# de0-orpsoc.net
KiCad netlist of a schematic drawn in EAGLE
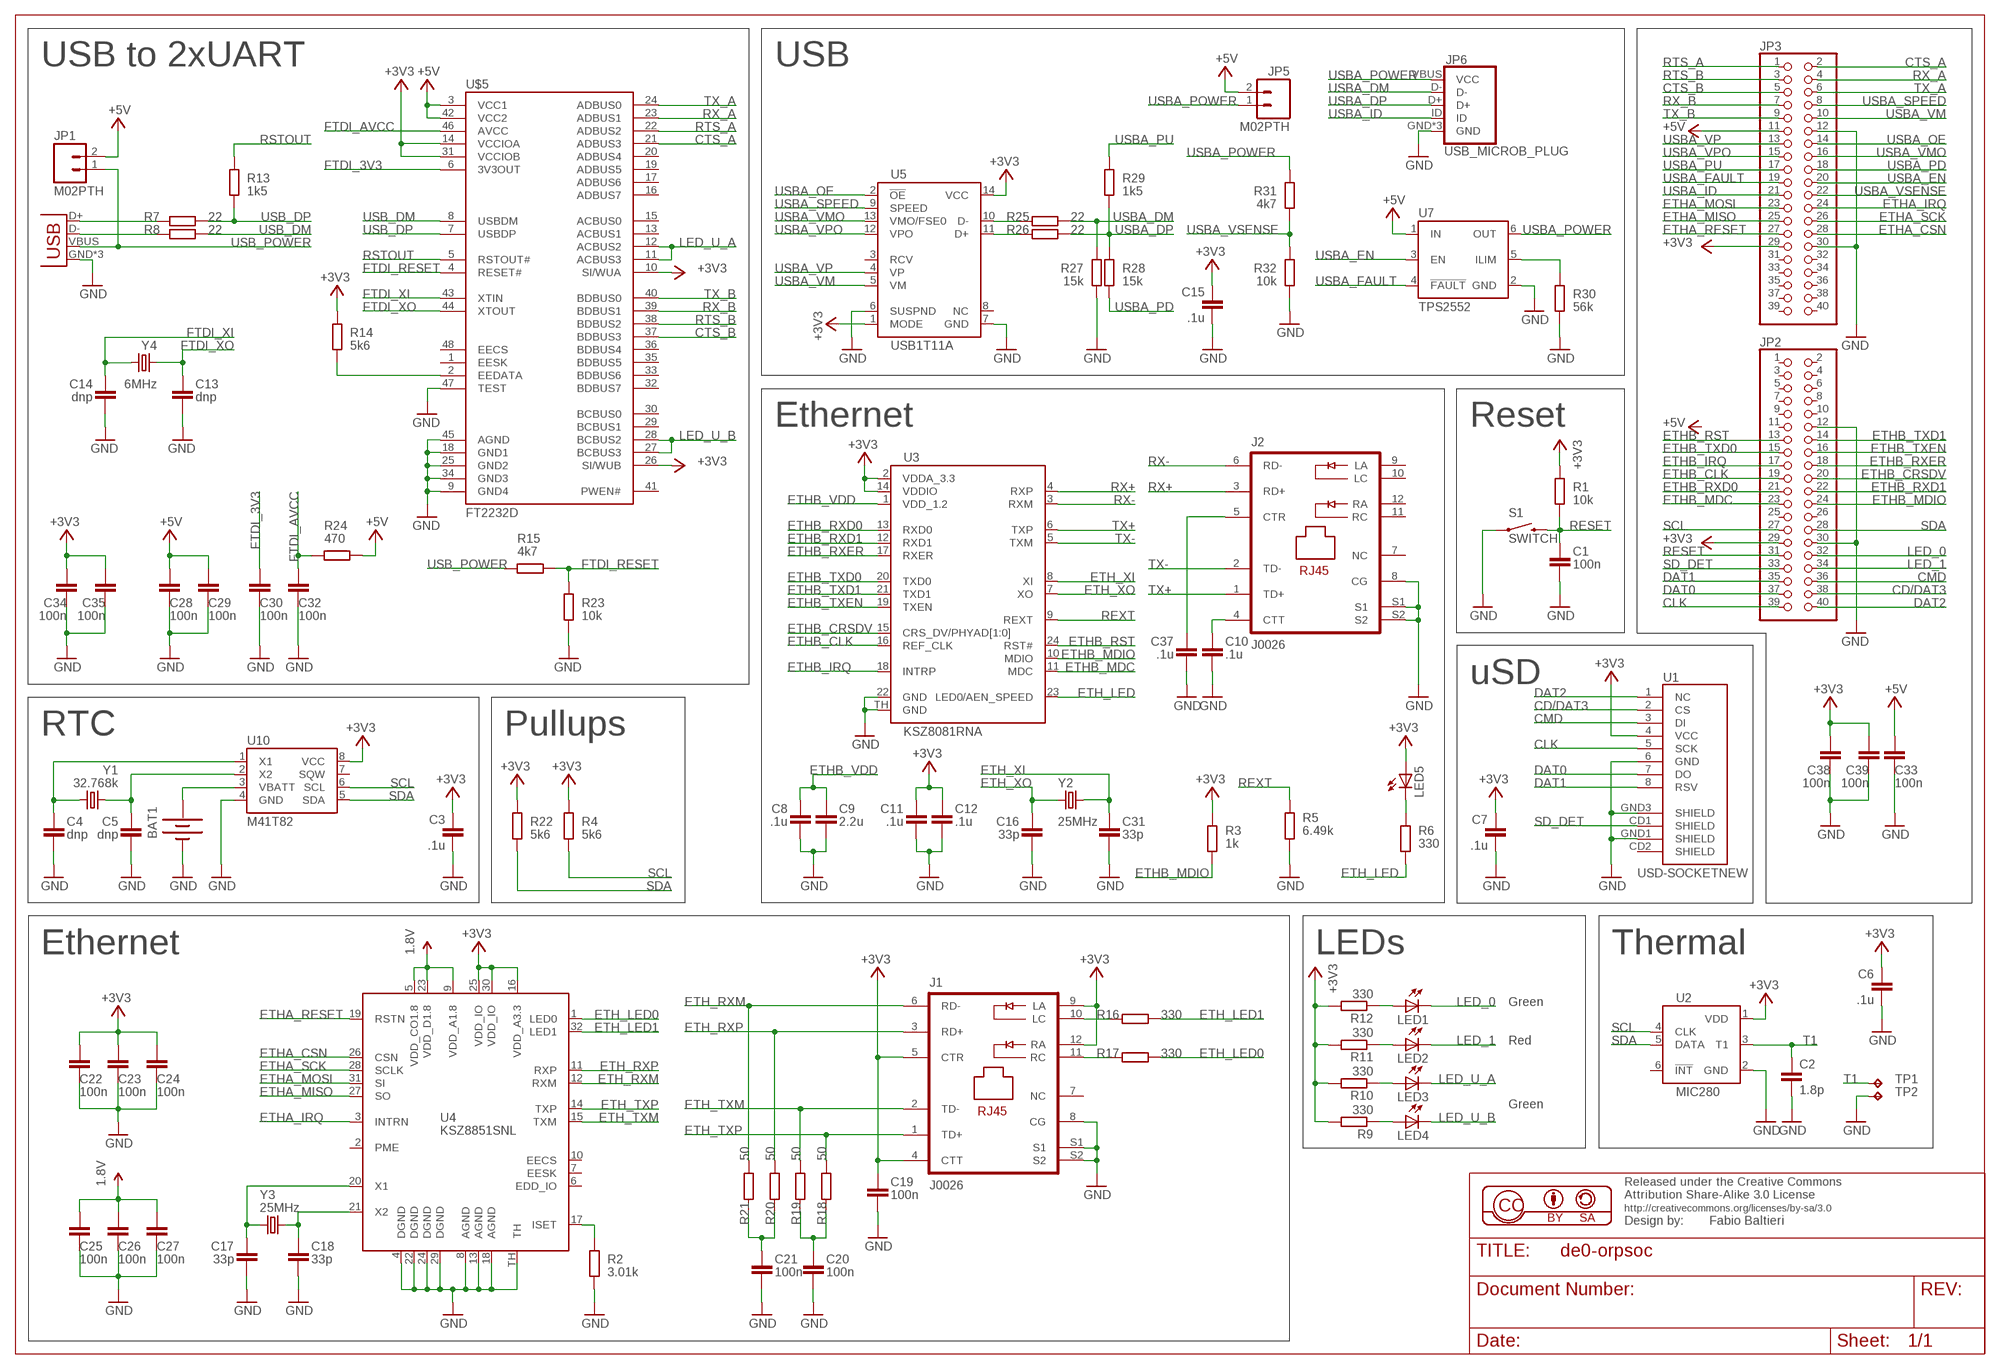
[diagram p0: schematic, sheet 1]

(export (version "E")
  (design (tool "Eeschema 10.0.6"))
  (components
    (comp (ref "BAT1")
      (value "BATTERY12PTH")
      (footprint "eagle-import:BATTCON_12MM_PTH")
      (libsource (lib "eagle-import") (part "BATTERY12PTH"))
    )
    (comp (ref "C1")
      (value "100n")
      (footprint "eagle-import:C0603")
      (libsource (lib "eagle-import") (part "C-EUC0603"))
    )
    (comp (ref "C2")
      (value "1.8p")
      (footprint "eagle-import:C0603")
      (libsource (lib "eagle-import") (part "C-EUC0603"))
    )
    (comp (ref "C3")
      (value ".1u")
      (footprint "eagle-import:C0603")
      (libsource (lib "eagle-import") (part "C-EUC0603"))
    )
    (comp (ref "C4")
      (value "dnp")
      (footprint "eagle-import:C0603")
      (libsource (lib "eagle-import") (part "C-EUC0603"))
    )
    (comp (ref "C5")
      (value "dnp")
      (footprint "eagle-import:C0603")
      (libsource (lib "eagle-import") (part "C-EUC0603"))
    )
    (comp (ref "C6")
      (value ".1u")
      (footprint "eagle-import:C0603")
      (libsource (lib "eagle-import") (part "C-EUC0603"))
    )
    (comp (ref "C7")
      (value ".1u")
      (footprint "eagle-import:C0603")
      (libsource (lib "eagle-import") (part "C-EUC0603"))
    )
    (comp (ref "C8")
      (value ".1u")
      (footprint "eagle-import:C0603")
      (libsource (lib "eagle-import") (part "C-EUC0603"))
    )
    (comp (ref "C9")
      (value "2.2u")
      (footprint "eagle-import:C0603")
      (libsource (lib "eagle-import") (part "C-EUC0603"))
    )
    (comp (ref "C10")
      (value ".1u")
      (footprint "eagle-import:C0603")
      (libsource (lib "eagle-import") (part "C-EUC0603"))
    )
    (comp (ref "C11")
      (value ".1u")
      (footprint "eagle-import:C0603")
      (libsource (lib "eagle-import") (part "C-EUC0603"))
    )
    (comp (ref "C12")
      (value ".1u")
      (footprint "eagle-import:C0603")
      (libsource (lib "eagle-import") (part "C-EUC0603"))
    )
    (comp (ref "C13")
      (value "dnp")
      (footprint "eagle-import:C0603")
      (libsource (lib "eagle-import") (part "C-EUC0603"))
    )
    (comp (ref "C14")
      (value "dnp")
      (footprint "eagle-import:C0603")
      (libsource (lib "eagle-import") (part "C-EUC0603"))
    )
    (comp (ref "C15")
      (value ".1u")
      (footprint "eagle-import:C0603")
      (libsource (lib "eagle-import") (part "C-EUC0603"))
    )
    (comp (ref "C16")
      (value "33p")
      (footprint "eagle-import:C0603")
      (libsource (lib "eagle-import") (part "C-EUC0603"))
    )
    (comp (ref "C17")
      (value "33p")
      (footprint "eagle-import:C0603")
      (libsource (lib "eagle-import") (part "C-EUC0603"))
    )
    (comp (ref "C18")
      (value "33p")
      (footprint "eagle-import:C0603")
      (libsource (lib "eagle-import") (part "C-EUC0603"))
    )
    (comp (ref "C19")
      (value "100n")
      (footprint "eagle-import:C0603")
      (libsource (lib "eagle-import") (part "C-EUC0603"))
    )
    (comp (ref "C20")
      (value "100n")
      (footprint "eagle-import:C0603")
      (libsource (lib "eagle-import") (part "C-EUC0603"))
    )
    (comp (ref "C21")
      (value "100n")
      (footprint "eagle-import:C0603")
      (libsource (lib "eagle-import") (part "C-EUC0603"))
    )
    (comp (ref "C22")
      (value "100n")
      (footprint "eagle-import:C0603")
      (libsource (lib "eagle-import") (part "C-EUC0603"))
    )
    (comp (ref "C23")
      (value "100n")
      (footprint "eagle-import:C0603")
      (libsource (lib "eagle-import") (part "C-EUC0603"))
    )
    (comp (ref "C24")
      (value "100n")
      (footprint "eagle-import:C0603")
      (libsource (lib "eagle-import") (part "C-EUC0603"))
    )
    (comp (ref "C25")
      (value "100n")
      (footprint "eagle-import:C0603")
      (libsource (lib "eagle-import") (part "C-EUC0603"))
    )
    (comp (ref "C26")
      (value "100n")
      (footprint "eagle-import:C0603")
      (libsource (lib "eagle-import") (part "C-EUC0603"))
    )
    (comp (ref "C27")
      (value "100n")
      (footprint "eagle-import:C0603")
      (libsource (lib "eagle-import") (part "C-EUC0603"))
    )
    (comp (ref "C28")
      (value "100n")
      (footprint "eagle-import:C0603")
      (libsource (lib "eagle-import") (part "C-EUC0603"))
    )
    (comp (ref "C29")
      (value "100n")
      (footprint "eagle-import:C0603")
      (libsource (lib "eagle-import") (part "C-EUC0603"))
    )
    (comp (ref "C30")
      (value "100n")
      (footprint "eagle-import:C0603")
      (libsource (lib "eagle-import") (part "C-EUC0603"))
    )
    (comp (ref "C31")
      (value "33p")
      (footprint "eagle-import:C0603")
      (libsource (lib "eagle-import") (part "C-EUC0603"))
    )
    (comp (ref "C32")
      (value "100n")
      (footprint "eagle-import:C0603")
      (libsource (lib "eagle-import") (part "C-EUC0603"))
    )
    (comp (ref "C33")
      (value "100n")
      (footprint "eagle-import:C0603")
      (libsource (lib "eagle-import") (part "C-EUC0603"))
    )
    (comp (ref "C34")
      (value "100n")
      (footprint "eagle-import:C0603")
      (libsource (lib "eagle-import") (part "C-EUC0603"))
    )
    (comp (ref "C35")
      (value "100n")
      (footprint "eagle-import:C0603")
      (libsource (lib "eagle-import") (part "C-EUC0603"))
    )
    (comp (ref "C37")
      (value ".1u")
      (footprint "eagle-import:C0603")
      (libsource (lib "eagle-import") (part "C-EUC0603"))
    )
    (comp (ref "C38")
      (value "100n")
      (footprint "eagle-import:C0603")
      (libsource (lib "eagle-import") (part "C-EUC0603"))
    )
    (comp (ref "C39")
      (value "100n")
      (footprint "eagle-import:C0603")
      (libsource (lib "eagle-import") (part "C-EUC0603"))
    )
    (comp (ref "J1")
      (value "J0026")
      (footprint "eagle-import:PJ-J0")
      (libsource (lib "eagle-import") (part "J0026"))
    )
    (comp (ref "J2")
      (value "J0026")
      (footprint "eagle-import:PJ-J0")
      (libsource (lib "eagle-import") (part "J0026"))
    )
    (comp (ref "JP1")
      (value "M02PTH")
      (footprint "eagle-import:1X02")
      (libsource (lib "eagle-import") (part "M02PTH"))
    )
    (comp (ref "JP2")
      (value "PINHD-2X20")
      (footprint "eagle-import:2X20")
      (libsource (lib "eagle-import") (part "PINHD-2X20"))
    )
    (comp (ref "JP3")
      (value "PINHD-2X20")
      (footprint "eagle-import:2X20")
      (libsource (lib "eagle-import") (part "PINHD-2X20"))
    )
    (comp (ref "JP5")
      (value "M02PTH")
      (footprint "eagle-import:1X02")
      (libsource (lib "eagle-import") (part "M02PTH"))
    )
    (comp (ref "JP6")
      (value "USB_MICROB_PLUG")
      (footprint "eagle-import:USB-MICROB")
      (libsource (lib "eagle-import") (part "USB_MICROB_PLUG"))
    )
    (comp (ref "JP10")
      (value "USB-MICROB")
      (footprint "eagle-import:USB-MICROB")
      (libsource (lib "eagle-import") (part "USB-MICROB"))
    )
    (comp (ref "LED1")
      (value "LEDCHIPLED_0805")
      (footprint "eagle-import:CHIPLED_0805")
      (libsource (lib "eagle-import") (part "LEDCHIPLED_0805"))
    )
    (comp (ref "LED2")
      (value "LEDCHIPLED_0805")
      (footprint "eagle-import:CHIPLED_0805")
      (libsource (lib "eagle-import") (part "LEDCHIPLED_0805"))
    )
    (comp (ref "LED3")
      (value "LEDCHIPLED_0805")
      (footprint "eagle-import:CHIPLED_0805")
      (libsource (lib "eagle-import") (part "LEDCHIPLED_0805"))
    )
    (comp (ref "LED4")
      (value "LEDCHIPLED_0805")
      (footprint "eagle-import:CHIPLED_0805")
      (libsource (lib "eagle-import") (part "LEDCHIPLED_0805"))
    )
    (comp (ref "LED5")
      (value "LEDCHIPLED_0805")
      (footprint "eagle-import:CHIPLED_0805")
      (libsource (lib "eagle-import") (part "LEDCHIPLED_0805"))
    )
    (comp (ref "R1")
      (value "10k")
      (footprint "eagle-import:R0603")
      (libsource (lib "eagle-import") (part "R-EU_R0603"))
    )
    (comp (ref "R2")
      (value "3.01k")
      (footprint "eagle-import:R0603")
      (libsource (lib "eagle-import") (part "R-EU_R0603"))
    )
    (comp (ref "R3")
      (value "1k")
      (footprint "eagle-import:R0603")
      (libsource (lib "eagle-import") (part "R-EU_R0603"))
    )
    (comp (ref "R4")
      (value "5k6")
      (footprint "eagle-import:R0603")
      (libsource (lib "eagle-import") (part "R-EU_R0603"))
    )
    (comp (ref "R5")
      (value "6.49k")
      (footprint "eagle-import:R0603")
      (libsource (lib "eagle-import") (part "R-EU_R0603"))
    )
    (comp (ref "R6")
      (value "330")
      (footprint "eagle-import:R0603")
      (libsource (lib "eagle-import") (part "R-EU_R0603"))
    )
    (comp (ref "R7")
      (value "22")
      (footprint "eagle-import:R0603")
      (libsource (lib "eagle-import") (part "R-EU_R0603"))
    )
    (comp (ref "R8")
      (value "22")
      (footprint "eagle-import:R0603")
      (libsource (lib "eagle-import") (part "R-EU_R0603"))
    )
    (comp (ref "R9")
      (value "330")
      (footprint "eagle-import:R0603")
      (libsource (lib "eagle-import") (part "R-EU_R0603"))
    )
    (comp (ref "R10")
      (value "330")
      (footprint "eagle-import:R0603")
      (libsource (lib "eagle-import") (part "R-EU_R0603"))
    )
    (comp (ref "R11")
      (value "330")
      (footprint "eagle-import:R0603")
      (libsource (lib "eagle-import") (part "R-EU_R0603"))
    )
    (comp (ref "R12")
      (value "330")
      (footprint "eagle-import:R0603")
      (libsource (lib "eagle-import") (part "R-EU_R0603"))
    )
    (comp (ref "R13")
      (value "1k5")
      (footprint "eagle-import:R0603")
      (libsource (lib "eagle-import") (part "R-EU_R0603"))
    )
    (comp (ref "R14")
      (value "5k6")
      (footprint "eagle-import:R0603")
      (libsource (lib "eagle-import") (part "R-EU_R0603"))
    )
    (comp (ref "R15")
      (value "4k7")
      (footprint "eagle-import:R0603")
      (libsource (lib "eagle-import") (part "R-EU_R0603"))
    )
    (comp (ref "R16")
      (value "330")
      (footprint "eagle-import:R0603")
      (libsource (lib "eagle-import") (part "R-EU_R0603"))
    )
    (comp (ref "R17")
      (value "330")
      (footprint "eagle-import:R0603")
      (libsource (lib "eagle-import") (part "R-EU_R0603"))
    )
    (comp (ref "R18")
      (value "50")
      (footprint "eagle-import:R0603")
      (libsource (lib "eagle-import") (part "R-EU_R0603"))
    )
    (comp (ref "R19")
      (value "50")
      (footprint "eagle-import:R0603")
      (libsource (lib "eagle-import") (part "R-EU_R0603"))
    )
    (comp (ref "R20")
      (value "50")
      (footprint "eagle-import:R0603")
      (libsource (lib "eagle-import") (part "R-EU_R0603"))
    )
    (comp (ref "R21")
      (value "50")
      (footprint "eagle-import:R0603")
      (libsource (lib "eagle-import") (part "R-EU_R0603"))
    )
    (comp (ref "R22")
      (value "5k6")
      (footprint "eagle-import:R0603")
      (libsource (lib "eagle-import") (part "R-EU_R0603"))
    )
    (comp (ref "R23")
      (value "10k")
      (footprint "eagle-import:R0603")
      (libsource (lib "eagle-import") (part "R-EU_R0603"))
    )
    (comp (ref "R24")
      (value "470")
      (footprint "eagle-import:R0603")
      (libsource (lib "eagle-import") (part "R-EU_R0603"))
    )
    (comp (ref "R25")
      (value "22")
      (footprint "eagle-import:R0603")
      (libsource (lib "eagle-import") (part "R-EU_R0603"))
    )
    (comp (ref "R26")
      (value "22")
      (footprint "eagle-import:R0603")
      (libsource (lib "eagle-import") (part "R-EU_R0603"))
    )
    (comp (ref "R27")
      (value "15k")
      (footprint "eagle-import:R0603")
      (libsource (lib "eagle-import") (part "R-EU_R0603"))
    )
    (comp (ref "R28")
      (value "15k")
      (footprint "eagle-import:R0603")
      (libsource (lib "eagle-import") (part "R-EU_R0603"))
    )
    (comp (ref "R29")
      (value "1k5")
      (footprint "eagle-import:R0603")
      (libsource (lib "eagle-import") (part "R-EU_R0603"))
    )
    (comp (ref "R30")
      (value "56k")
      (footprint "eagle-import:R0603")
      (libsource (lib "eagle-import") (part "R-EU_R0603"))
    )
    (comp (ref "R31")
      (value "4k7")
      (footprint "eagle-import:R0603")
      (libsource (lib "eagle-import") (part "R-EU_R0603"))
    )
    (comp (ref "R32")
      (value "10k")
      (footprint "eagle-import:R0603")
      (libsource (lib "eagle-import") (part "R-EU_R0603"))
    )
    (comp (ref "S1")
      (value "SWITCH")
      (footprint "eagle-import:TACTILE_SWITCH_SMD")
      (libsource (lib "eagle-import") (part "SWITCH-MOMENTARY-2SMD"))
    )
    (comp (ref "TP1")
      (value "TPTP12R")
      (footprint "eagle-import:TP12R")
      (libsource (lib "eagle-import") (part "TPTP12R"))
    )
    (comp (ref "TP2")
      (value "TPTP12R")
      (footprint "eagle-import:TP12R")
      (libsource (lib "eagle-import") (part "TPTP12R"))
    )
    (comp (ref "U$5")
      (value "FT2232D")
      (footprint "eagle-import:LQFP-48")
      (libsource (lib "eagle-import") (part "FT2232D"))
    )
    (comp (ref "U1")
      (value "USD-SOCKETNEW")
      (footprint "eagle-import:MICRO-SD-SOCKET-PP")
      (libsource (lib "eagle-import") (part "USD-SOCKETNEW"))
    )
    (comp (ref "U2")
      (value "MIC280")
      (footprint "eagle-import:SOT23-6L")
      (libsource (lib "eagle-import") (part "MIC280"))
    )
    (comp (ref "U3")
      (value "KSZ8081RNA")
      (footprint "eagle-import:QFN24")
      (libsource (lib "eagle-import") (part "KSZ8081"))
    )
    (comp (ref "U4")
      (value "KSZ8851SNL")
      (footprint "eagle-import:MLF32-TH")
      (libsource (lib "eagle-import") (part "KSZ8851SNL"))
    )
    (comp (ref "U5")
      (value "USB1T11A")
      (footprint "eagle-import:SOIC14")
      (libsource (lib "eagle-import") (part "USB1T11A"))
    )
    (comp (ref "U7")
      (value "TPS2552")
      (footprint "eagle-import:SOT23-6L")
      (libsource (lib "eagle-import") (part "TPS2552"))
    )
    (comp (ref "U10")
      (value "M41T82")
      (footprint "eagle-import:SO08")
      (libsource (lib "eagle-import") (part "DS1307SO8"))
    )
    (comp (ref "Y1")
      (value "32.768k")
      (footprint "eagle-import:CRYSTAL-32KHZ-SMD")
      (libsource (lib "eagle-import") (part "SparkFun-FreqCtrl_CRYSTAL32-SMD"))
    )
    (comp (ref "Y2")
      (value "25MHz")
      (footprint "eagle-import:CRYSTAL-SMD-5X3")
      (libsource (lib "eagle-import") (part "CRYSTAL5X3"))
    )
    (comp (ref "Y3")
      (value "25MHz")
      (footprint "eagle-import:CRYSTAL-SMD-5X3")
      (libsource (lib "eagle-import") (part "CRYSTAL5X3"))
    )
    (comp (ref "Y4")
      (value "6MHz")
      (footprint "eagle-import:CRYSTAL-SMD-5X3")
      (libsource (lib "eagle-import") (part "CRYSTAL5X3"))
    )
  )
  (nets
    (net (code "1") (name "+3V3") (class "Default")
      (node (ref "C11") (pin "1") (pinfunction "1_1") (pintype "passive"))
      (node (ref "C12") (pin "1") (pinfunction "1_1") (pintype "passive"))
      (node (ref "C15") (pin "1") (pinfunction "1_1") (pintype "passive"))
      (node (ref "C19") (pin "1") (pinfunction "1_1") (pintype "passive"))
      (node (ref "C22") (pin "1") (pinfunction "1_1") (pintype "passive"))
      (node (ref "C23") (pin "1") (pinfunction "1_1") (pintype "passive"))
      (node (ref "C24") (pin "1") (pinfunction "1_1") (pintype "passive"))
      (node (ref "C3") (pin "1") (pinfunction "1_1") (pintype "passive"))
      (node (ref "C34") (pin "1") (pinfunction "1_1") (pintype "passive"))
      (node (ref "C35") (pin "1") (pinfunction "1_1") (pintype "passive"))
      (node (ref "C38") (pin "1") (pinfunction "1_1") (pintype "passive"))
      (node (ref "C39") (pin "1") (pinfunction "1_1") (pintype "passive"))
      (node (ref "C6") (pin "1") (pinfunction "1_1") (pintype "passive"))
      (node (ref "C7") (pin "1") (pinfunction "1_1") (pintype "passive"))
      (node (ref "J1") (pin "12") (pinfunction "RA_12") (pintype "passive"))
      (node (ref "J1") (pin "4") (pinfunction "CTT_4") (pintype "bidirectional"))
      (node (ref "J1") (pin "5") (pinfunction "CTR_5") (pintype "bidirectional"))
      (node (ref "J1") (pin "9") (pinfunction "LA_9") (pintype "passive"))
      (node (ref "JP2") (pin "29") (pinfunction "29_29") (pintype "passive"))
      (node (ref "JP3") (pin "29") (pinfunction "29_29") (pintype "passive"))
      (node (ref "LED5") (pin "A") (pinfunction "A_A") (pintype "passive"))
      (node (ref "R1") (pin "2") (pinfunction "2_2") (pintype "passive"))
      (node (ref "R10") (pin "2") (pinfunction "2_2") (pintype "passive"))
      (node (ref "R11") (pin "2") (pinfunction "2_2") (pintype "passive"))
      (node (ref "R12") (pin "2") (pinfunction "2_2") (pintype "passive"))
      (node (ref "R14") (pin "1") (pinfunction "1_1") (pintype "passive"))
      (node (ref "R22") (pin "1") (pinfunction "1_1") (pintype "passive"))
      (node (ref "R3") (pin "2") (pinfunction "2_2") (pintype "passive"))
      (node (ref "R4") (pin "1") (pinfunction "1_1") (pintype "passive"))
      (node (ref "R9") (pin "2") (pinfunction "2_2") (pintype "passive"))
      (node (ref "U$5") (pin "10") (pinfunction "SI/WUA_10") (pintype "bidirectional"))
      (node (ref "U$5") (pin "14") (pinfunction "VCCIOA_14") (pintype "power_in"))
      (node (ref "U$5") (pin "26") (pinfunction "SI/WUB_26") (pintype "bidirectional"))
      (node (ref "U$5") (pin "31") (pinfunction "VCCIOB_31") (pintype "bidirectional"))
      (node (ref "U1") (pin "4") (pinfunction "VCC_4") (pintype "bidirectional"))
      (node (ref "U10") (pin "8") (pinfunction "VCC_8") (pintype "bidirectional"))
      (node (ref "U2") (pin "1") (pinfunction "VDD_1") (pintype "bidirectional"))
      (node (ref "U3") (pin "14") (pinfunction "VDDIO_14") (pintype "bidirectional"))
      (node (ref "U3") (pin "2") (pinfunction "VDDA_3.3_2") (pintype "bidirectional"))
      (node (ref "U4") (pin "16") (pinfunction "VDD_A3.3_16") (pintype "bidirectional"))
      (node (ref "U4") (pin "25") (pinfunction "VDD_IO_25") (pintype "bidirectional"))
      (node (ref "U4") (pin "30") (pinfunction "VDD_IO_30") (pintype "bidirectional"))
      (node (ref "U5") (pin "1") (pinfunction "MODE_1") (pintype "bidirectional"))
      (node (ref "U5") (pin "14") (pinfunction "VCC_14") (pintype "bidirectional"))
    )
    (net (code "2") (name "+5V") (class "Default")
      (node (ref "C28") (pin "1") (pinfunction "1_1") (pintype "passive"))
      (node (ref "C29") (pin "1") (pinfunction "1_1") (pintype "passive"))
      (node (ref "C33") (pin "1") (pinfunction "1_1") (pintype "passive"))
      (node (ref "JP1") (pin "2") (pinfunction "2_2") (pintype "passive"))
      (node (ref "JP3") (pin "11") (pinfunction "11_11") (pintype "passive"))
      (node (ref "JP5") (pin "2") (pinfunction "2_2") (pintype "passive"))
      (node (ref "R24") (pin "2") (pinfunction "2_2") (pintype "passive"))
      (node (ref "U$5") (pin "3") (pinfunction "VCC1_3") (pintype "power_in"))
      (node (ref "U$5") (pin "42") (pinfunction "VCC2_42") (pintype "power_in"))
      (node (ref "U7") (pin "1") (pinfunction "IN_1") (pintype "bidirectional"))
    )
    (net (code "3") (name "/CD{slash}DAT3") (class "Default")
      (node (ref "JP2") (pin "38") (pinfunction "38_38") (pintype "passive"))
      (node (ref "U1") (pin "2") (pinfunction "CS_2") (pintype "bidirectional"))
    )
    (net (code "4") (name "/CLK") (class "Default")
      (node (ref "JP2") (pin "39") (pinfunction "39_39") (pintype "passive"))
      (node (ref "U1") (pin "5") (pinfunction "SCK_5") (pintype "bidirectional"))
    )
    (net (code "5") (name "/CMD") (class "Default")
      (node (ref "JP2") (pin "36") (pinfunction "36_36") (pintype "passive"))
      (node (ref "U1") (pin "3") (pinfunction "DI_3") (pintype "bidirectional"))
    )
    (net (code "6") (name "/CTS_A") (class "Default")
      (node (ref "JP3") (pin "2") (pinfunction "2_2") (pintype "passive"))
      (node (ref "U$5") (pin "21") (pinfunction "ADBUS3_21") (pintype "bidirectional"))
    )
    (net (code "7") (name "/CTS_B") (class "Default")
      (node (ref "JP3") (pin "5") (pinfunction "5_5") (pintype "passive"))
      (node (ref "U$5") (pin "37") (pinfunction "BDBUS3_37") (pintype "input"))
    )
    (net (code "8") (name "/DAT0") (class "Default")
      (node (ref "JP2") (pin "37") (pinfunction "37_37") (pintype "passive"))
      (node (ref "U1") (pin "7") (pinfunction "DO_7") (pintype "bidirectional"))
    )
    (net (code "9") (name "/DAT1") (class "Default")
      (node (ref "JP2") (pin "35") (pinfunction "35_35") (pintype "passive"))
      (node (ref "U1") (pin "8") (pinfunction "RSV_8") (pintype "bidirectional"))
    )
    (net (code "10") (name "/DAT2") (class "Default")
      (node (ref "JP2") (pin "40") (pinfunction "40_40") (pintype "passive"))
      (node (ref "U1") (pin "1") (pinfunction "NC_1") (pintype "bidirectional"))
    )
    (net (code "11") (name "/ETHA_CSN") (class "Default")
      (node (ref "JP3") (pin "28") (pinfunction "28_28") (pintype "passive"))
      (node (ref "U4") (pin "26") (pinfunction "CSN_26") (pintype "bidirectional"))
    )
    (net (code "12") (name "/ETHA_IRQ") (class "Default")
      (node (ref "JP3") (pin "24") (pinfunction "24_24") (pintype "passive"))
      (node (ref "U4") (pin "3") (pinfunction "INTRN_3") (pintype "bidirectional"))
    )
    (net (code "13") (name "/ETHA_MISO") (class "Default")
      (node (ref "JP3") (pin "25") (pinfunction "25_25") (pintype "passive"))
      (node (ref "U4") (pin "27") (pinfunction "SO_27") (pintype "bidirectional"))
    )
    (net (code "14") (name "/ETHA_MOSI") (class "Default")
      (node (ref "JP3") (pin "23") (pinfunction "23_23") (pintype "passive"))
      (node (ref "U4") (pin "31") (pinfunction "SI_31") (pintype "bidirectional"))
    )
    (net (code "15") (name "/ETHA_RESET") (class "Default")
      (node (ref "JP3") (pin "27") (pinfunction "27_27") (pintype "passive"))
      (node (ref "U4") (pin "19") (pinfunction "RSTN_19") (pintype "bidirectional"))
    )
    (net (code "16") (name "/ETHA_SCK") (class "Default")
      (node (ref "JP3") (pin "26") (pinfunction "26_26") (pintype "passive"))
      (node (ref "U4") (pin "28") (pinfunction "SCLK_28") (pintype "bidirectional"))
    )
    (net (code "17") (name "/ETHB_CLK") (class "Default")
      (node (ref "JP2") (pin "19") (pinfunction "19_19") (pintype "passive"))
      (node (ref "U3") (pin "16") (pinfunction "REF_CLK_16") (pintype "bidirectional"))
    )
    (net (code "18") (name "/ETHB_CRSDV") (class "Default")
      (node (ref "JP2") (pin "20") (pinfunction "20_20") (pintype "passive"))
      (node (ref "U3") (pin "15") (pinfunction "CRS_DV/PHYAD[1:0]_15") (pintype "bidirectional"))
    )
    (net (code "19") (name "/ETHB_IRQ") (class "Default")
      (node (ref "JP2") (pin "17") (pinfunction "17_17") (pintype "passive"))
      (node (ref "U3") (pin "18") (pinfunction "INTRP_18") (pintype "bidirectional"))
    )
    (net (code "20") (name "/ETHB_MDC") (class "Default")
      (node (ref "JP2") (pin "23") (pinfunction "23_23") (pintype "passive"))
      (node (ref "U3") (pin "11") (pinfunction "MDC_11") (pintype "bidirectional"))
    )
    (net (code "21") (name "/ETHB_MDIO") (class "Default")
      (node (ref "JP2") (pin "24") (pinfunction "24_24") (pintype "passive"))
      (node (ref "R3") (pin "1") (pinfunction "1_1") (pintype "passive"))
      (node (ref "U3") (pin "10") (pinfunction "MDIO_10") (pintype "bidirectional"))
    )
    (net (code "22") (name "/ETHB_RST") (class "Default")
      (node (ref "JP2") (pin "13") (pinfunction "13_13") (pintype "passive"))
      (node (ref "U3") (pin "24") (pinfunction "RST#_24") (pintype "bidirectional"))
    )
    (net (code "23") (name "/ETHB_RXD0") (class "Default")
      (node (ref "JP2") (pin "21") (pinfunction "21_21") (pintype "passive"))
      (node (ref "U3") (pin "13") (pinfunction "RXD0_13") (pintype "bidirectional"))
    )
    (net (code "24") (name "/ETHB_RXD1") (class "Default")
      (node (ref "JP2") (pin "22") (pinfunction "22_22") (pintype "passive"))
      (node (ref "U3") (pin "12") (pinfunction "RXD1_12") (pintype "bidirectional"))
    )
    (net (code "25") (name "/ETHB_RXER") (class "Default")
      (node (ref "JP2") (pin "18") (pinfunction "18_18") (pintype "passive"))
      (node (ref "U3") (pin "17") (pinfunction "RXER_17") (pintype "bidirectional"))
    )
    (net (code "26") (name "/ETHB_TXD0") (class "Default")
      (node (ref "JP2") (pin "15") (pinfunction "15_15") (pintype "passive"))
      (node (ref "U3") (pin "20") (pinfunction "TXD0_20") (pintype "bidirectional"))
    )
    (net (code "27") (name "/ETHB_TXD1") (class "Default")
      (node (ref "JP2") (pin "14") (pinfunction "14_14") (pintype "passive"))
      (node (ref "U3") (pin "21") (pinfunction "TXD1_21") (pintype "bidirectional"))
    )
    (net (code "28") (name "/ETHB_TXEN") (class "Default")
      (node (ref "JP2") (pin "16") (pinfunction "16_16") (pintype "passive"))
      (node (ref "U3") (pin "19") (pinfunction "TXEN_19") (pintype "bidirectional"))
    )
    (net (code "29") (name "/ETHB_VDD") (class "Default")
      (node (ref "C8") (pin "1") (pinfunction "1_1") (pintype "passive"))
      (node (ref "C9") (pin "1") (pinfunction "1_1") (pintype "passive"))
      (node (ref "U3") (pin "1") (pinfunction "VDD_1.2_1") (pintype "bidirectional"))
    )
    (net (code "30") (name "/ETH_LED") (class "Default")
      (node (ref "R6") (pin "1") (pinfunction "1_1") (pintype "passive"))
      (node (ref "U3") (pin "23") (pinfunction "LED0/AEN_SPEED_23") (pintype "bidirectional"))
    )
    (net (code "31") (name "/ETH_LED0") (class "Default")
      (node (ref "R17") (pin "2") (pinfunction "2_2") (pintype "passive"))
      (node (ref "U4") (pin "1") (pinfunction "LED0_1") (pintype "bidirectional"))
    )
    (net (code "32") (name "/ETH_LED1") (class "Default")
      (node (ref "R16") (pin "2") (pinfunction "2_2") (pintype "passive"))
      (node (ref "U4") (pin "32") (pinfunction "LED1_32") (pintype "bidirectional"))
    )
    (net (code "33") (name "/ETH_RXM") (class "Default")
      (node (ref "J1") (pin "6") (pinfunction "RD-_6") (pintype "bidirectional"))
      (node (ref "R21") (pin "2") (pinfunction "2_2") (pintype "passive"))
      (node (ref "U4") (pin "12") (pinfunction "RXM_12") (pintype "bidirectional"))
    )
    (net (code "34") (name "/ETH_RXP") (class "Default")
      (node (ref "J1") (pin "3") (pinfunction "RD+_3") (pintype "bidirectional"))
      (node (ref "R20") (pin "2") (pinfunction "2_2") (pintype "passive"))
      (node (ref "U4") (pin "11") (pinfunction "RXP_11") (pintype "bidirectional"))
    )
    (net (code "35") (name "/ETH_TXM") (class "Default")
      (node (ref "J1") (pin "2") (pinfunction "TD-_2") (pintype "bidirectional"))
      (node (ref "R19") (pin "2") (pinfunction "2_2") (pintype "passive"))
      (node (ref "U4") (pin "15") (pinfunction "TXM_15") (pintype "bidirectional"))
    )
    (net (code "36") (name "/ETH_TXP") (class "Default")
      (node (ref "J1") (pin "1") (pinfunction "TD+_1") (pintype "bidirectional"))
      (node (ref "R18") (pin "2") (pinfunction "2_2") (pintype "passive"))
      (node (ref "U4") (pin "14") (pinfunction "TXP_14") (pintype "bidirectional"))
    )
    (net (code "37") (name "/ETH_XI") (class "Default")
      (node (ref "C31") (pin "1") (pinfunction "1_1") (pintype "passive"))
      (node (ref "U3") (pin "8") (pinfunction "XI_8") (pintype "bidirectional"))
      (node (ref "Y2") (pin "3") (pinfunction "2_3") (pintype "passive"))
    )
    (net (code "38") (name "/ETH_XO") (class "Default")
      (node (ref "C16") (pin "1") (pinfunction "1_1") (pintype "passive"))
      (node (ref "U3") (pin "7") (pinfunction "XO_7") (pintype "bidirectional"))
      (node (ref "Y2") (pin "1") (pinfunction "1_1") (pintype "passive"))
    )
    (net (code "39") (name "/FTDI_3V3") (class "Default")
      (node (ref "C30") (pin "1") (pinfunction "1_1") (pintype "passive"))
      (node (ref "U$5") (pin "6") (pinfunction "3V3OUT_6") (pintype "output"))
    )
    (net (code "40") (name "/FTDI_AVCC") (class "Default")
      (node (ref "C32") (pin "1") (pinfunction "1_1") (pintype "passive"))
      (node (ref "R24") (pin "1") (pinfunction "1_1") (pintype "passive"))
      (node (ref "U$5") (pin "46") (pinfunction "AVCC_46") (pintype "bidirectional"))
    )
    (net (code "41") (name "/FTDI_RESET") (class "Default")
      (node (ref "R15") (pin "2") (pinfunction "2_2") (pintype "passive"))
      (node (ref "R23") (pin "1") (pinfunction "1_1") (pintype "passive"))
      (node (ref "U$5") (pin "4") (pinfunction "RESET#_4") (pintype "bidirectional"))
    )
    (net (code "42") (name "/FTDI_XI") (class "Default")
      (node (ref "C14") (pin "1") (pinfunction "1_1") (pintype "passive"))
      (node (ref "U$5") (pin "43") (pinfunction "XTIN_43") (pintype "bidirectional"))
      (node (ref "Y4") (pin "3") (pinfunction "2_3") (pintype "passive"))
    )
    (net (code "43") (name "/FTDI_XO") (class "Default")
      (node (ref "C13") (pin "1") (pinfunction "1_1") (pintype "passive"))
      (node (ref "U$5") (pin "44") (pinfunction "XTOUT_44") (pintype "bidirectional"))
      (node (ref "Y4") (pin "1") (pinfunction "1_1") (pintype "passive"))
    )
    (net (code "44") (name "/LED_0") (class "Default")
      (node (ref "JP2") (pin "32") (pinfunction "32_32") (pintype "passive"))
      (node (ref "LED1") (pin "C") (pinfunction "C_C") (pintype "passive"))
    )
    (net (code "45") (name "/LED_1") (class "Default")
      (node (ref "JP2") (pin "34") (pinfunction "34_34") (pintype "passive"))
      (node (ref "LED2") (pin "C") (pinfunction "C_C") (pintype "passive"))
    )
    (net (code "46") (name "/LED_U_A") (class "Default")
      (node (ref "LED3") (pin "C") (pinfunction "C_C") (pintype "passive"))
      (node (ref "U$5") (pin "11") (pinfunction "ACBUS3_11") (pintype "bidirectional"))
      (node (ref "U$5") (pin "12") (pinfunction "ACBUS2_12") (pintype "bidirectional"))
    )
    (net (code "47") (name "/LED_U_B") (class "Default")
      (node (ref "LED4") (pin "C") (pinfunction "C_C") (pintype "passive"))
      (node (ref "U$5") (pin "27") (pinfunction "BCBUS3_27") (pintype "bidirectional"))
      (node (ref "U$5") (pin "28") (pinfunction "BCBUS2_28") (pintype "bidirectional"))
    )
    (net (code "48") (name "/RESET") (class "Default")
      (node (ref "C1") (pin "1") (pinfunction "1_1") (pintype "passive"))
      (node (ref "JP2") (pin "31") (pinfunction "31_31") (pintype "passive"))
      (node (ref "R1") (pin "1") (pinfunction "1_1") (pintype "passive"))
      (node (ref "S1") (pin "3") (pinfunction "2_3") (pintype "passive"))
    )
    (net (code "49") (name "/REXT") (class "Default")
      (node (ref "R5") (pin "2") (pinfunction "2_2") (pintype "passive"))
      (node (ref "U3") (pin "9") (pinfunction "REXT_9") (pintype "bidirectional"))
    )
    (net (code "50") (name "/RSTOUT") (class "Default")
      (node (ref "R13") (pin "1") (pinfunction "1_1") (pintype "passive"))
      (node (ref "U$5") (pin "5") (pinfunction "RSTOUT#_5") (pintype "bidirectional"))
    )
    (net (code "51") (name "/RTS_A") (class "Default")
      (node (ref "JP3") (pin "1") (pinfunction "1_1") (pintype "passive"))
      (node (ref "U$5") (pin "22") (pinfunction "ADBUS2_22") (pintype "bidirectional"))
    )
    (net (code "52") (name "/RTS_B") (class "Default")
      (node (ref "JP3") (pin "3") (pinfunction "3_3") (pintype "passive"))
      (node (ref "U$5") (pin "38") (pinfunction "BDBUS2_38") (pintype "output"))
    )
    (net (code "53") (name "/RX+") (class "Default")
      (node (ref "J2") (pin "3") (pinfunction "RD+_3") (pintype "bidirectional"))
      (node (ref "U3") (pin "4") (pinfunction "RXP_4") (pintype "bidirectional"))
    )
    (net (code "54") (name "/RX-") (class "Default")
      (node (ref "J2") (pin "6") (pinfunction "RD-_6") (pintype "bidirectional"))
      (node (ref "U3") (pin "3") (pinfunction "RXM_3") (pintype "bidirectional"))
    )
    (net (code "55") (name "/RX_A") (class "Default")
      (node (ref "JP3") (pin "4") (pinfunction "4_4") (pintype "passive"))
      (node (ref "U$5") (pin "23") (pinfunction "ADBUS1_23") (pintype "bidirectional"))
    )
    (net (code "56") (name "/RX_B") (class "Default")
      (node (ref "JP3") (pin "7") (pinfunction "7_7") (pintype "passive"))
      (node (ref "U$5") (pin "39") (pinfunction "BDBUS1_39") (pintype "input"))
    )
    (net (code "57") (name "/SCL") (class "Default")
      (node (ref "JP2") (pin "27") (pinfunction "27_27") (pintype "passive"))
      (node (ref "R4") (pin "2") (pinfunction "2_2") (pintype "passive"))
      (node (ref "U10") (pin "6") (pinfunction "SCL_6") (pintype "bidirectional"))
      (node (ref "U2") (pin "4") (pinfunction "CLK_4") (pintype "bidirectional"))
    )
    (net (code "58") (name "/SDA") (class "Default")
      (node (ref "JP2") (pin "28") (pinfunction "28_28") (pintype "passive"))
      (node (ref "R22") (pin "2") (pinfunction "2_2") (pintype "passive"))
      (node (ref "U10") (pin "5") (pinfunction "SDA_5") (pintype "bidirectional"))
      (node (ref "U2") (pin "5") (pinfunction "DATA_5") (pintype "bidirectional"))
    )
    (net (code "59") (name "/SD_DET") (class "Default")
      (node (ref "JP2") (pin "33") (pinfunction "33_33") (pintype "passive"))
      (node (ref "U1") (pin "CD1") (pinfunction "SHIELD_CD1") (pintype "bidirectional"))
    )
    (net (code "60") (name "/T1") (class "Default")
      (node (ref "C2") (pin "1") (pinfunction "1_1") (pintype "passive"))
      (node (ref "TP1") (pin "TP") (pinfunction "TP_TP") (pintype "input"))
      (node (ref "U2") (pin "3") (pinfunction "T1_3") (pintype "bidirectional"))
    )
    (net (code "61") (name "/TX+") (class "Default")
      (node (ref "J2") (pin "1") (pinfunction "TD+_1") (pintype "bidirectional"))
      (node (ref "U3") (pin "6") (pinfunction "TXP_6") (pintype "bidirectional"))
    )
    (net (code "62") (name "/TX-") (class "Default")
      (node (ref "J2") (pin "2") (pinfunction "TD-_2") (pintype "bidirectional"))
      (node (ref "U3") (pin "5") (pinfunction "TXM_5") (pintype "bidirectional"))
    )
    (net (code "63") (name "/TX_A") (class "Default")
      (node (ref "JP3") (pin "6") (pinfunction "6_6") (pintype "passive"))
      (node (ref "U$5") (pin "24") (pinfunction "ADBUS0_24") (pintype "bidirectional"))
    )
    (net (code "64") (name "/TX_B") (class "Default")
      (node (ref "JP3") (pin "9") (pinfunction "9_9") (pintype "passive"))
      (node (ref "U$5") (pin "40") (pinfunction "BDBUS0_40") (pintype "output"))
    )
    (net (code "65") (name "/USBA_DM") (class "Default")
      (node (ref "JP6") (pin "D-") (pinfunction "D-_D-") (pintype "bidirectional"))
      (node (ref "R25") (pin "2") (pinfunction "2_2") (pintype "passive"))
      (node (ref "R27") (pin "1") (pinfunction "1_1") (pintype "passive"))
    )
    (net (code "66") (name "/USBA_DP") (class "Default")
      (node (ref "JP6") (pin "D+") (pinfunction "D+_D+") (pintype "bidirectional"))
      (node (ref "R26") (pin "2") (pinfunction "2_2") (pintype "passive"))
      (node (ref "R28") (pin "1") (pinfunction "1_1") (pintype "passive"))
      (node (ref "R29") (pin "2") (pinfunction "2_2") (pintype "passive"))
    )
    (net (code "67") (name "/USBA_EN") (class "Default")
      (node (ref "JP3") (pin "20") (pinfunction "20_20") (pintype "passive"))
      (node (ref "U7") (pin "3") (pinfunction "EN_3") (pintype "bidirectional"))
    )
    (net (code "68") (name "/USBA_FAULT") (class "Default")
      (node (ref "JP3") (pin "19") (pinfunction "19_19") (pintype "passive"))
      (node (ref "U7") (pin "4") (pinfunction "~{FAULT}_4") (pintype "bidirectional"))
    )
    (net (code "69") (name "/USBA_ID") (class "Default")
      (node (ref "JP3") (pin "21") (pinfunction "21_21") (pintype "passive"))
      (node (ref "JP6") (pin "ID") (pinfunction "ID_ID") (pintype "bidirectional"))
    )
    (net (code "70") (name "/USBA_OE") (class "Default")
      (node (ref "JP3") (pin "14") (pinfunction "14_14") (pintype "passive"))
      (node (ref "U5") (pin "2") (pinfunction "~{OE}_2") (pintype "bidirectional"))
    )
    (net (code "71") (name "/USBA_PD") (class "Default")
      (node (ref "JP3") (pin "18") (pinfunction "18_18") (pintype "passive"))
      (node (ref "R28") (pin "2") (pinfunction "2_2") (pintype "passive"))
    )
    (net (code "72") (name "/USBA_POWER") (class "Default")
      (node (ref "JP5") (pin "1") (pinfunction "1_1") (pintype "passive"))
      (node (ref "JP6") (pin "VBUS") (pinfunction "VCC_VBUS") (pintype "bidirectional"))
      (node (ref "R31") (pin "1") (pinfunction "1_1") (pintype "passive"))
      (node (ref "U7") (pin "6") (pinfunction "OUT_6") (pintype "bidirectional"))
    )
    (net (code "73") (name "/USBA_PU") (class "Default")
      (node (ref "JP3") (pin "17") (pinfunction "17_17") (pintype "passive"))
      (node (ref "R29") (pin "1") (pinfunction "1_1") (pintype "passive"))
    )
    (net (code "74") (name "/USBA_SPEED") (class "Default")
      (node (ref "JP3") (pin "8") (pinfunction "8_8") (pintype "passive"))
      (node (ref "U5") (pin "9") (pinfunction "SPEED_9") (pintype "bidirectional"))
    )
    (net (code "75") (name "/USBA_VM") (class "Default")
      (node (ref "JP3") (pin "10") (pinfunction "10_10") (pintype "passive"))
      (node (ref "U5") (pin "5") (pinfunction "VM_5") (pintype "bidirectional"))
    )
    (net (code "76") (name "/USBA_VMO") (class "Default")
      (node (ref "JP3") (pin "16") (pinfunction "16_16") (pintype "passive"))
      (node (ref "U5") (pin "13") (pinfunction "VMO/FSE0_13") (pintype "bidirectional"))
    )
    (net (code "77") (name "/USBA_VP") (class "Default")
      (node (ref "JP3") (pin "13") (pinfunction "13_13") (pintype "passive"))
      (node (ref "U5") (pin "4") (pinfunction "VP_4") (pintype "bidirectional"))
    )
    (net (code "78") (name "/USBA_VPO") (class "Default")
      (node (ref "JP3") (pin "15") (pinfunction "15_15") (pintype "passive"))
      (node (ref "U5") (pin "12") (pinfunction "VPO_12") (pintype "bidirectional"))
    )
    (net (code "79") (name "/USBA_VSENSE") (class "Default")
      (node (ref "JP3") (pin "22") (pinfunction "22_22") (pintype "passive"))
      (node (ref "R31") (pin "2") (pinfunction "2_2") (pintype "passive"))
      (node (ref "R32") (pin "1") (pinfunction "1_1") (pintype "passive"))
    )
    (net (code "80") (name "/USB_DM") (class "Default")
      (node (ref "R8") (pin "2") (pinfunction "2_2") (pintype "passive"))
      (node (ref "U$5") (pin "8") (pinfunction "USBDM_8") (pintype "bidirectional"))
    )
    (net (code "81") (name "/USB_DP") (class "Default")
      (node (ref "R13") (pin "2") (pinfunction "2_2") (pintype "passive"))
      (node (ref "R7") (pin "2") (pinfunction "2_2") (pintype "passive"))
      (node (ref "U$5") (pin "7") (pinfunction "USBDP_7") (pintype "bidirectional"))
    )
    (net (code "82") (name "/USB_POWER") (class "Default")
      (node (ref "JP1") (pin "1") (pinfunction "1_1") (pintype "passive"))
      (node (ref "JP10") (pin "VBUS") (pinfunction "VBUS_VBUS") (pintype "bidirectional"))
      (node (ref "R15") (pin "1") (pinfunction "1_1") (pintype "passive"))
    )
    (net (code "83") (name "1.8V") (class "Default")
      (node (ref "C25") (pin "1") (pinfunction "1_1") (pintype "passive"))
      (node (ref "C26") (pin "1") (pinfunction "1_1") (pintype "passive"))
      (node (ref "C27") (pin "1") (pinfunction "1_1") (pintype "passive"))
      (node (ref "U4") (pin "23") (pinfunction "VDD_D1.8_23") (pintype "bidirectional"))
      (node (ref "U4") (pin "5") (pinfunction "VDD_CO1.8_5") (pintype "bidirectional"))
      (node (ref "U4") (pin "9") (pinfunction "VDD_A1.8_9") (pintype "bidirectional"))
    )
    (net (code "84") (name "GND") (class "Default")
      (node (ref "BAT1") (pin "GND") (pinfunction "-_GND") (pintype "power_in"))
      (node (ref "C1") (pin "2") (pinfunction "2_2") (pintype "passive"))
      (node (ref "C10") (pin "2") (pinfunction "2_2") (pintype "passive"))
      (node (ref "C11") (pin "2") (pinfunction "2_2") (pintype "passive"))
      (node (ref "C12") (pin "2") (pinfunction "2_2") (pintype "passive"))
      (node (ref "C13") (pin "2") (pinfunction "2_2") (pintype "passive"))
      (node (ref "C14") (pin "2") (pinfunction "2_2") (pintype "passive"))
      (node (ref "C15") (pin "2") (pinfunction "2_2") (pintype "passive"))
      (node (ref "C16") (pin "2") (pinfunction "2_2") (pintype "passive"))
      (node (ref "C17") (pin "2") (pinfunction "2_2") (pintype "passive"))
      (node (ref "C18") (pin "2") (pinfunction "2_2") (pintype "passive"))
      (node (ref "C19") (pin "2") (pinfunction "2_2") (pintype "passive"))
      (node (ref "C2") (pin "2") (pinfunction "2_2") (pintype "passive"))
      (node (ref "C20") (pin "2") (pinfunction "2_2") (pintype "passive"))
      (node (ref "C21") (pin "2") (pinfunction "2_2") (pintype "passive"))
      (node (ref "C22") (pin "2") (pinfunction "2_2") (pintype "passive"))
      (node (ref "C23") (pin "2") (pinfunction "2_2") (pintype "passive"))
      (node (ref "C24") (pin "2") (pinfunction "2_2") (pintype "passive"))
      (node (ref "C25") (pin "2") (pinfunction "2_2") (pintype "passive"))
      (node (ref "C26") (pin "2") (pinfunction "2_2") (pintype "passive"))
      (node (ref "C27") (pin "2") (pinfunction "2_2") (pintype "passive"))
      (node (ref "C28") (pin "2") (pinfunction "2_2") (pintype "passive"))
      (node (ref "C29") (pin "2") (pinfunction "2_2") (pintype "passive"))
      (node (ref "C3") (pin "2") (pinfunction "2_2") (pintype "passive"))
      (node (ref "C30") (pin "2") (pinfunction "2_2") (pintype "passive"))
      (node (ref "C31") (pin "2") (pinfunction "2_2") (pintype "passive"))
      (node (ref "C32") (pin "2") (pinfunction "2_2") (pintype "passive"))
      (node (ref "C33") (pin "2") (pinfunction "2_2") (pintype "passive"))
      (node (ref "C34") (pin "2") (pinfunction "2_2") (pintype "passive"))
      (node (ref "C35") (pin "2") (pinfunction "2_2") (pintype "passive"))
      (node (ref "C37") (pin "2") (pinfunction "2_2") (pintype "passive"))
      (node (ref "C38") (pin "2") (pinfunction "2_2") (pintype "passive"))
      (node (ref "C39") (pin "2") (pinfunction "2_2") (pintype "passive"))
      (node (ref "C4") (pin "2") (pinfunction "2_2") (pintype "passive"))
      (node (ref "C5") (pin "2") (pinfunction "2_2") (pintype "passive"))
      (node (ref "C6") (pin "2") (pinfunction "2_2") (pintype "passive"))
      (node (ref "C7") (pin "2") (pinfunction "2_2") (pintype "passive"))
      (node (ref "C8") (pin "2") (pinfunction "2_2") (pintype "passive"))
      (node (ref "C9") (pin "2") (pinfunction "2_2") (pintype "passive"))
      (node (ref "J1") (pin "8") (pinfunction "CG_8") (pintype "passive"))
      (node (ref "J1") (pin "S1") (pinfunction "S1_S1") (pintype "passive"))
      (node (ref "J1") (pin "S2") (pinfunction "S2_S2") (pintype "passive"))
      (node (ref "J2") (pin "8") (pinfunction "CG_8") (pintype "passive"))
      (node (ref "J2") (pin "S1") (pinfunction "S1_S1") (pintype "passive"))
      (node (ref "J2") (pin "S2") (pinfunction "S2_S2") (pintype "passive"))
      (node (ref "JP10") (pin "GND") (pinfunction "GND_GND") (pintype "bidirectional"))
      (node (ref "JP10") (pin "MT1") (pinfunction "GND_MT1") (pintype "bidirectional"))
      (node (ref "JP10") (pin "MT2") (pinfunction "GND_MT2") (pintype "bidirectional"))
      (node (ref "JP2") (pin "12") (pinfunction "12_12") (pintype "passive"))
      (node (ref "JP2") (pin "30") (pinfunction "30_30") (pintype "passive"))
      (node (ref "JP3") (pin "12") (pinfunction "12_12") (pintype "passive"))
      (node (ref "JP3") (pin "30") (pinfunction "30_30") (pintype "passive"))
      (node (ref "JP6") (pin "GND") (pinfunction "GND_GND") (pintype "bidirectional"))
      (node (ref "JP6") (pin "MT1") (pinfunction "GND_MT1") (pintype "bidirectional"))
      (node (ref "JP6") (pin "MT2") (pinfunction "GND_MT2") (pintype "bidirectional"))
      (node (ref "R2") (pin "2") (pinfunction "2_2") (pintype "passive"))
      (node (ref "R23") (pin "2") (pinfunction "2_2") (pintype "passive"))
      (node (ref "R27") (pin "2") (pinfunction "2_2") (pintype "passive"))
      (node (ref "R30") (pin "2") (pinfunction "2_2") (pintype "passive"))
      (node (ref "R32") (pin "2") (pinfunction "2_2") (pintype "passive"))
      (node (ref "R5") (pin "1") (pinfunction "1_1") (pintype "passive"))
      (node (ref "S1") (pin "1") (pinfunction "1_1") (pintype "passive"))
      (node (ref "TP2") (pin "TP") (pinfunction "TP_TP") (pintype "input"))
      (node (ref "U$5") (pin "18") (pinfunction "GND1_18") (pintype "power_in"))
      (node (ref "U$5") (pin "25") (pinfunction "GND2_25") (pintype "power_in"))
      (node (ref "U$5") (pin "34") (pinfunction "GND3_34") (pintype "power_in"))
      (node (ref "U$5") (pin "45") (pinfunction "AGND_45") (pintype "power_in"))
      (node (ref "U$5") (pin "47") (pinfunction "TEST_47") (pintype "input"))
      (node (ref "U$5") (pin "9") (pinfunction "GND4_9") (pintype "bidirectional"))
      (node (ref "U1") (pin "6") (pinfunction "GND_6") (pintype "bidirectional"))
      (node (ref "U1") (pin "GND1") (pinfunction "SHIELD_GND1") (pintype "bidirectional"))
      (node (ref "U1") (pin "GND3") (pinfunction "SHIELD_GND3") (pintype "bidirectional"))
      (node (ref "U10") (pin "4") (pinfunction "GND_4") (pintype "bidirectional"))
      (node (ref "U2") (pin "2") (pinfunction "GND_2") (pintype "bidirectional"))
      (node (ref "U3") (pin "22") (pinfunction "GND_22") (pintype "bidirectional"))
      (node (ref "U3") (pin "TH") (pinfunction "GND_TH") (pintype "bidirectional"))
      (node (ref "U4") (pin "13") (pinfunction "AGND_13") (pintype "bidirectional"))
      (node (ref "U4") (pin "18") (pinfunction "AGND_18") (pintype "bidirectional"))
      (node (ref "U4") (pin "22") (pinfunction "DGND_22") (pintype "bidirectional"))
      (node (ref "U4") (pin "24") (pinfunction "DGND_24") (pintype "bidirectional"))
      (node (ref "U4") (pin "29") (pinfunction "DGND_29") (pintype "bidirectional"))
      (node (ref "U4") (pin "4") (pinfunction "DGND_4") (pintype "bidirectional"))
      (node (ref "U4") (pin "8") (pinfunction "AGND_8") (pintype "bidirectional"))
      (node (ref "U4") (pin "TH") (pinfunction "TH_TH") (pintype "bidirectional"))
      (node (ref "U5") (pin "6") (pinfunction "SUSPND_6") (pintype "bidirectional"))
      (node (ref "U5") (pin "7") (pinfunction "GND_7") (pintype "bidirectional"))
      (node (ref "U7") (pin "2") (pinfunction "GND_2") (pintype "bidirectional"))
    )
    (net (code "85") (name "Net-(BAT1-+)") (class "Default")
      (node (ref "BAT1") (pin "VCC@1") (pinfunction "+_VCC@1") (pintype "power_in"))
      (node (ref "U10") (pin "3") (pinfunction "VBATT_3") (pintype "bidirectional"))
    )
    (net (code "86") (name "Net-(C20-Pad1)") (class "Default")
      (node (ref "C20") (pin "1") (pinfunction "1_1") (pintype "passive"))
      (node (ref "R18") (pin "1") (pinfunction "1_1") (pintype "passive"))
      (node (ref "R19") (pin "1") (pinfunction "1_1") (pintype "passive"))
    )
    (net (code "87") (name "Net-(C21-Pad1)") (class "Default")
      (node (ref "C21") (pin "1") (pinfunction "1_1") (pintype "passive"))
      (node (ref "R20") (pin "1") (pinfunction "1_1") (pintype "passive"))
      (node (ref "R21") (pin "1") (pinfunction "1_1") (pintype "passive"))
    )
    (net (code "88") (name "Net-(J1-LC)") (class "Default")
      (node (ref "J1") (pin "10") (pinfunction "LC_10") (pintype "passive"))
      (node (ref "R16") (pin "1") (pinfunction "1_1") (pintype "passive"))
    )
    (net (code "89") (name "Net-(J1-RC)") (class "Default")
      (node (ref "J1") (pin "11") (pinfunction "RC_11") (pintype "passive"))
      (node (ref "R17") (pin "1") (pinfunction "1_1") (pintype "passive"))
    )
    (net (code "90") (name "Net-(J2-CTR)") (class "Default")
      (node (ref "C37") (pin "1") (pinfunction "1_1") (pintype "passive"))
      (node (ref "J2") (pin "5") (pinfunction "CTR_5") (pintype "bidirectional"))
    )
    (net (code "91") (name "Net-(J2-CTT)") (class "Default")
      (node (ref "C10") (pin "1") (pinfunction "1_1") (pintype "passive"))
      (node (ref "J2") (pin "4") (pinfunction "CTT_4") (pintype "bidirectional"))
    )
    (net (code "92") (name "Net-(JP10-PadD+)") (class "Default")
      (node (ref "JP10") (pin "D+") (pinfunction "D+_D+") (pintype "bidirectional"))
      (node (ref "R7") (pin "1") (pinfunction "1_1") (pintype "passive"))
    )
    (net (code "93") (name "Net-(JP10-PadD-)") (class "Default")
      (node (ref "JP10") (pin "D-") (pinfunction "D-_D-") (pintype "bidirectional"))
      (node (ref "R8") (pin "1") (pinfunction "1_1") (pintype "passive"))
    )
    (net (code "94") (name "Net-(LED1-PadA)") (class "Default")
      (node (ref "LED1") (pin "A") (pinfunction "A_A") (pintype "passive"))
      (node (ref "R12") (pin "1") (pinfunction "1_1") (pintype "passive"))
    )
    (net (code "95") (name "Net-(LED2-PadA)") (class "Default")
      (node (ref "LED2") (pin "A") (pinfunction "A_A") (pintype "passive"))
      (node (ref "R11") (pin "1") (pinfunction "1_1") (pintype "passive"))
    )
    (net (code "96") (name "Net-(LED3-PadA)") (class "Default")
      (node (ref "LED3") (pin "A") (pinfunction "A_A") (pintype "passive"))
      (node (ref "R10") (pin "1") (pinfunction "1_1") (pintype "passive"))
    )
    (net (code "97") (name "Net-(LED4-PadA)") (class "Default")
      (node (ref "LED4") (pin "A") (pinfunction "A_A") (pintype "passive"))
      (node (ref "R9") (pin "1") (pinfunction "1_1") (pintype "passive"))
    )
    (net (code "98") (name "Net-(LED5-PadC)") (class "Default")
      (node (ref "LED5") (pin "C") (pinfunction "C_C") (pintype "passive"))
      (node (ref "R6") (pin "2") (pinfunction "2_2") (pintype "passive"))
    )
    (net (code "99") (name "Net-(U$5-EEDATA)") (class "Default")
      (node (ref "R14") (pin "2") (pinfunction "2_2") (pintype "passive"))
      (node (ref "U$5") (pin "2") (pinfunction "EEDATA_2") (pintype "bidirectional"))
    )
    (net (code "100") (name "Net-(U4-ISET)") (class "Default")
      (node (ref "R2") (pin "1") (pinfunction "1_1") (pintype "passive"))
      (node (ref "U4") (pin "17") (pinfunction "ISET_17") (pintype "bidirectional"))
    )
    (net (code "101") (name "Net-(U4-X1)") (class "Default")
      (node (ref "C17") (pin "1") (pinfunction "1_1") (pintype "passive"))
      (node (ref "U4") (pin "20") (pinfunction "X1_20") (pintype "bidirectional"))
      (node (ref "Y3") (pin "1") (pinfunction "1_1") (pintype "passive"))
    )
    (net (code "102") (name "Net-(U4-X2)") (class "Default")
      (node (ref "C18") (pin "1") (pinfunction "1_1") (pintype "passive"))
      (node (ref "U4") (pin "21") (pinfunction "X2_21") (pintype "bidirectional"))
      (node (ref "Y3") (pin "3") (pinfunction "2_3") (pintype "passive"))
    )
    (net (code "103") (name "Net-(U5-D+)") (class "Default")
      (node (ref "R26") (pin "1") (pinfunction "1_1") (pintype "passive"))
      (node (ref "U5") (pin "11") (pinfunction "D+_11") (pintype "bidirectional"))
    )
    (net (code "104") (name "Net-(U5-D-)") (class "Default")
      (node (ref "R25") (pin "1") (pinfunction "1_1") (pintype "passive"))
      (node (ref "U5") (pin "10") (pinfunction "D-_10") (pintype "bidirectional"))
    )
    (net (code "105") (name "Net-(U7-ILIM)") (class "Default")
      (node (ref "R30") (pin "1") (pinfunction "1_1") (pintype "passive"))
      (node (ref "U7") (pin "5") (pinfunction "ILIM_5") (pintype "bidirectional"))
    )
    (net (code "106") (name "Net-(U10-X1)") (class "Default")
      (node (ref "C4") (pin "1") (pinfunction "1_1") (pintype "passive"))
      (node (ref "U10") (pin "1") (pinfunction "X1_1") (pintype "bidirectional"))
      (node (ref "Y1") (pin "X2") (pinfunction "2_X2") (pintype "passive"))
    )
    (net (code "107") (name "Net-(U10-X2)") (class "Default")
      (node (ref "C5") (pin "1") (pinfunction "1_1") (pintype "passive"))
      (node (ref "U10") (pin "2") (pinfunction "X2_2") (pintype "bidirectional"))
      (node (ref "Y1") (pin "X1") (pinfunction "1_X1") (pintype "passive"))
    )
    (net (code "108") (name "unconnected-(J1-NC-Pad7)") (class "Default")
      (node (ref "J1") (pin "7") (pinfunction "NC_7") (pintype "passive"))
    )
    (net (code "109") (name "unconnected-(J2-LA-Pad9)") (class "Default")
      (node (ref "J2") (pin "9") (pinfunction "LA_9") (pintype "passive"))
    )
    (net (code "110") (name "unconnected-(J2-LC-Pad10)") (class "Default")
      (node (ref "J2") (pin "10") (pinfunction "LC_10") (pintype "passive"))
    )
    (net (code "111") (name "unconnected-(J2-NC-Pad7)") (class "Default")
      (node (ref "J2") (pin "7") (pinfunction "NC_7") (pintype "passive"))
    )
    (net (code "112") (name "unconnected-(J2-RA-Pad12)") (class "Default")
      (node (ref "J2") (pin "12") (pinfunction "RA_12") (pintype "passive"))
    )
    (net (code "113") (name "unconnected-(J2-RC-Pad11)") (class "Default")
      (node (ref "J2") (pin "11") (pinfunction "RC_11") (pintype "passive"))
    )
    (net (code "114") (name "unconnected-(JP2-Pad1)") (class "Default")
      (node (ref "JP2") (pin "1") (pinfunction "1_1") (pintype "passive"))
    )
    (net (code "115") (name "unconnected-(JP2-Pad2)") (class "Default")
      (node (ref "JP2") (pin "2") (pinfunction "2_2") (pintype "passive"))
    )
    (net (code "116") (name "unconnected-(JP2-Pad3)") (class "Default")
      (node (ref "JP2") (pin "3") (pinfunction "3_3") (pintype "passive"))
    )
    (net (code "117") (name "unconnected-(JP2-Pad4)") (class "Default")
      (node (ref "JP2") (pin "4") (pinfunction "4_4") (pintype "passive"))
    )
    (net (code "118") (name "unconnected-(JP2-Pad5)") (class "Default")
      (node (ref "JP2") (pin "5") (pinfunction "5_5") (pintype "passive"))
    )
    (net (code "119") (name "unconnected-(JP2-Pad6)") (class "Default")
      (node (ref "JP2") (pin "6") (pinfunction "6_6") (pintype "passive"))
    )
    (net (code "120") (name "unconnected-(JP2-Pad7)") (class "Default")
      (node (ref "JP2") (pin "7") (pinfunction "7_7") (pintype "passive"))
    )
    (net (code "121") (name "unconnected-(JP2-Pad8)") (class "Default")
      (node (ref "JP2") (pin "8") (pinfunction "8_8") (pintype "passive"))
    )
    (net (code "122") (name "unconnected-(JP2-Pad9)") (class "Default")
      (node (ref "JP2") (pin "9") (pinfunction "9_9") (pintype "passive"))
    )
    (net (code "123") (name "unconnected-(JP2-Pad10)") (class "Default")
      (node (ref "JP2") (pin "10") (pinfunction "10_10") (pintype "passive"))
    )
    (net (code "124") (name "unconnected-(JP2-Pad11)") (class "Default")
      (node (ref "JP2") (pin "11") (pinfunction "11_11") (pintype "passive"))
    )
    (net (code "125") (name "unconnected-(JP2-Pad25)") (class "Default")
      (node (ref "JP2") (pin "25") (pinfunction "25_25") (pintype "passive"))
    )
    (net (code "126") (name "unconnected-(JP2-Pad26)") (class "Default")
      (node (ref "JP2") (pin "26") (pinfunction "26_26") (pintype "passive"))
    )
    (net (code "127") (name "unconnected-(JP3-Pad31)") (class "Default")
      (node (ref "JP3") (pin "31") (pinfunction "31_31") (pintype "passive"))
    )
    (net (code "128") (name "unconnected-(JP3-Pad32)") (class "Default")
      (node (ref "JP3") (pin "32") (pinfunction "32_32") (pintype "passive"))
    )
    (net (code "129") (name "unconnected-(JP3-Pad33)") (class "Default")
      (node (ref "JP3") (pin "33") (pinfunction "33_33") (pintype "passive"))
    )
    (net (code "130") (name "unconnected-(JP3-Pad34)") (class "Default")
      (node (ref "JP3") (pin "34") (pinfunction "34_34") (pintype "passive"))
    )
    (net (code "131") (name "unconnected-(JP3-Pad35)") (class "Default")
      (node (ref "JP3") (pin "35") (pinfunction "35_35") (pintype "passive"))
    )
    (net (code "132") (name "unconnected-(JP3-Pad36)") (class "Default")
      (node (ref "JP3") (pin "36") (pinfunction "36_36") (pintype "passive"))
    )
    (net (code "133") (name "unconnected-(JP3-Pad37)") (class "Default")
      (node (ref "JP3") (pin "37") (pinfunction "37_37") (pintype "passive"))
    )
    (net (code "134") (name "unconnected-(JP3-Pad38)") (class "Default")
      (node (ref "JP3") (pin "38") (pinfunction "38_38") (pintype "passive"))
    )
    (net (code "135") (name "unconnected-(JP3-Pad39)") (class "Default")
      (node (ref "JP3") (pin "39") (pinfunction "39_39") (pintype "passive"))
    )
    (net (code "136") (name "unconnected-(JP3-Pad40)") (class "Default")
      (node (ref "JP3") (pin "40") (pinfunction "40_40") (pintype "passive"))
    )
    (net (code "137") (name "unconnected-(U$5-ACBUS0-Pad15)") (class "Default")
      (node (ref "U$5") (pin "15") (pinfunction "ACBUS0_15") (pintype "bidirectional"))
    )
    (net (code "138") (name "unconnected-(U$5-ACBUS1-Pad13)") (class "Default")
      (node (ref "U$5") (pin "13") (pinfunction "ACBUS1_13") (pintype "bidirectional"))
    )
    (net (code "139") (name "unconnected-(U$5-ADBUS4-Pad20)") (class "Default")
      (node (ref "U$5") (pin "20") (pinfunction "ADBUS4_20") (pintype "bidirectional"))
    )
    (net (code "140") (name "unconnected-(U$5-ADBUS5-Pad19)") (class "Default")
      (node (ref "U$5") (pin "19") (pinfunction "ADBUS5_19") (pintype "bidirectional"))
    )
    (net (code "141") (name "unconnected-(U$5-ADBUS6-Pad17)") (class "Default")
      (node (ref "U$5") (pin "17") (pinfunction "ADBUS6_17") (pintype "bidirectional"))
    )
    (net (code "142") (name "unconnected-(U$5-ADBUS7-Pad16)") (class "Default")
      (node (ref "U$5") (pin "16") (pinfunction "ADBUS7_16") (pintype "bidirectional"))
    )
    (net (code "143") (name "unconnected-(U$5-BCBUS0-Pad30)") (class "Default")
      (node (ref "U$5") (pin "30") (pinfunction "BCBUS0_30") (pintype "bidirectional"))
    )
    (net (code "144") (name "unconnected-(U$5-BCBUS1-Pad29)") (class "Default")
      (node (ref "U$5") (pin "29") (pinfunction "BCBUS1_29") (pintype "bidirectional"))
    )
    (net (code "145") (name "unconnected-(U$5-BDBUS4-Pad36)") (class "Default")
      (node (ref "U$5") (pin "36") (pinfunction "BDBUS4_36") (pintype "output"))
    )
    (net (code "146") (name "unconnected-(U$5-BDBUS5-Pad35)") (class "Default")
      (node (ref "U$5") (pin "35") (pinfunction "BDBUS5_35") (pintype "input"))
    )
    (net (code "147") (name "unconnected-(U$5-BDBUS6-Pad33)") (class "Default")
      (node (ref "U$5") (pin "33") (pinfunction "BDBUS6_33") (pintype "input"))
    )
    (net (code "148") (name "unconnected-(U$5-BDBUS7-Pad32)") (class "Default")
      (node (ref "U$5") (pin "32") (pinfunction "BDBUS7_32") (pintype "input"))
    )
    (net (code "149") (name "unconnected-(U$5-EECS-Pad48)") (class "Default")
      (node (ref "U$5") (pin "48") (pinfunction "EECS_48") (pintype "bidirectional"))
    )
    (net (code "150") (name "unconnected-(U$5-EESK-Pad1)") (class "Default")
      (node (ref "U$5") (pin "1") (pinfunction "EESK_1") (pintype "bidirectional"))
    )
    (net (code "151") (name "unconnected-(U$5-PWEN#-Pad41)") (class "Default")
      (node (ref "U$5") (pin "41") (pinfunction "PWEN#_41") (pintype "bidirectional"))
    )
    (net (code "152") (name "unconnected-(U1-SHIELD-PadCD2)") (class "Default")
      (node (ref "U1") (pin "CD2") (pinfunction "SHIELD_CD2") (pintype "bidirectional"))
    )
    (net (code "153") (name "unconnected-(U2-~{INT}-Pad6)") (class "Default")
      (node (ref "U2") (pin "6") (pinfunction "~{INT}_6") (pintype "bidirectional"))
    )
    (net (code "154") (name "unconnected-(U4-EDD_IO-Pad6)") (class "Default")
      (node (ref "U4") (pin "6") (pinfunction "EDD_IO_6") (pintype "bidirectional"))
    )
    (net (code "155") (name "unconnected-(U4-EECS-Pad10)") (class "Default")
      (node (ref "U4") (pin "10") (pinfunction "EECS_10") (pintype "bidirectional"))
    )
    (net (code "156") (name "unconnected-(U4-EESK-Pad7)") (class "Default")
      (node (ref "U4") (pin "7") (pinfunction "EESK_7") (pintype "bidirectional"))
    )
    (net (code "157") (name "unconnected-(U4-PME-Pad2)") (class "Default")
      (node (ref "U4") (pin "2") (pinfunction "PME_2") (pintype "bidirectional"))
    )
    (net (code "158") (name "unconnected-(U5-NC-Pad8)") (class "Default")
      (node (ref "U5") (pin "8") (pinfunction "NC_8") (pintype "bidirectional"))
    )
    (net (code "159") (name "unconnected-(U5-RCV-Pad3)") (class "Default")
      (node (ref "U5") (pin "3") (pinfunction "RCV_3") (pintype "bidirectional"))
    )
    (net (code "160") (name "unconnected-(U10-SQW-Pad7)") (class "Default")
      (node (ref "U10") (pin "7") (pinfunction "SQW_7") (pintype "bidirectional"))
    )
  )
)
